# UI.net
KiCad netlist of a schematic drawn in EAGLE
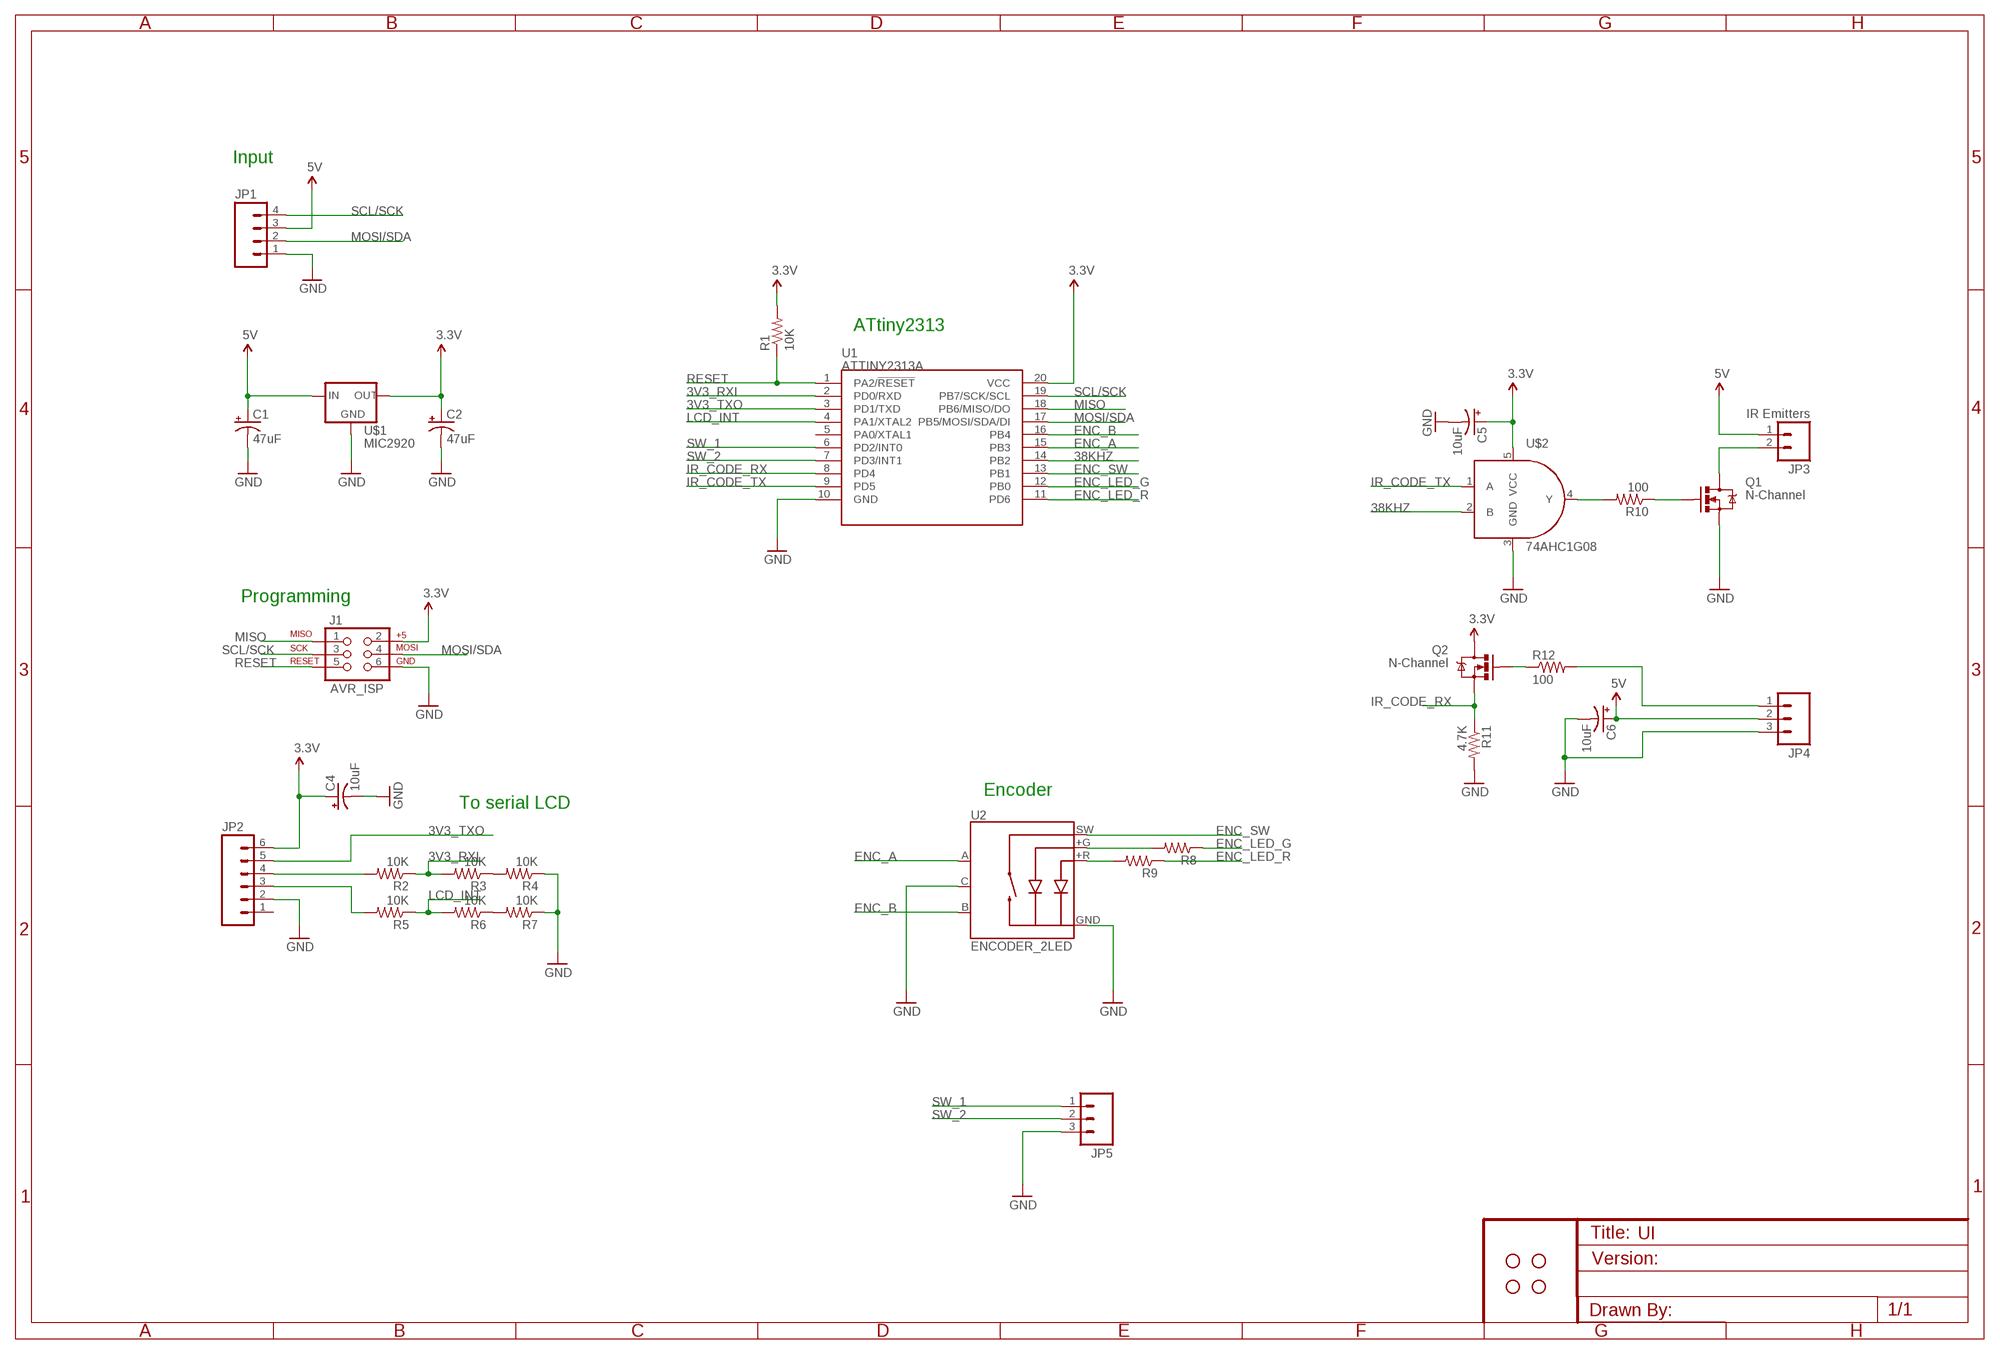
[diagram p0: schematic, sheet 1]

(export (version "E")
  (design (tool "Eeschema 10.0.6"))
  (components
    (comp (ref "C1")
      (value "47uF")
      (footprint "eagle-import:CPOL-RADIAL-10UF-25V")
      (libsource (lib "eagle-import") (part "CAP_POLPTH2"))
    )
    (comp (ref "C2")
      (value "47uF")
      (footprint "eagle-import:CPOL-RADIAL-10UF-25V")
      (libsource (lib "eagle-import") (part "CAP_POLPTH2"))
    )
    (comp (ref "C4")
      (value "10uF")
      (footprint "eagle-import:EIA3216")
      (libsource (lib "eagle-import") (part "CAP_POL1206"))
    )
    (comp (ref "C5")
      (value "10uF")
      (footprint "eagle-import:EIA3216")
      (libsource (lib "eagle-import") (part "CAP_POL1206"))
    )
    (comp (ref "C6")
      (value "10uF")
      (footprint "eagle-import:EIA3216")
      (libsource (lib "eagle-import") (part "CAP_POL1206"))
    )
    (comp (ref "J1")
      (value "AVR_ISP")
      (footprint "eagle-import:2X3")
      (libsource (lib "eagle-import") (part "AVR_SPI_PRG_6PTH"))
    )
    (comp (ref "JP1")
      (value "M04POLAR")
      (footprint "eagle-import:MOLEX-1X4")
      (libsource (lib "eagle-import") (part "M04POLAR"))
    )
    (comp (ref "JP2")
      (value "M06POLAR")
      (footprint "eagle-import:MOLEX-1X6")
      (libsource (lib "eagle-import") (part "M06POLAR"))
    )
    (comp (ref "JP3")
      (value "IR Emitters")
      (footprint "eagle-import:SCREWTERMINAL-3.5MM-2")
      (libsource (lib "eagle-import") (part "M023.5MM"))
    )
    (comp (ref "JP4")
      (value "M03PTH")
      (footprint "eagle-import:1X03")
      (libsource (lib "eagle-import") (part "M03PTH"))
    )
    (comp (ref "JP5")
      (value "M03PTH")
      (footprint "eagle-import:1X03")
      (libsource (lib "eagle-import") (part "M03PTH"))
    )
    (comp (ref "Q1")
      (value "N-Channel")
      (footprint "eagle-import:SOT23")
      (libsource (lib "eagle-import") (part "MOSFET-NCHANNELBSS138"))
    )
    (comp (ref "Q2")
      (value "N-Channel")
      (footprint "eagle-import:SOT23")
      (libsource (lib "eagle-import") (part "MOSFET-NCHANNELBSS138"))
    )
    (comp (ref "R1")
      (value "10K")
      (footprint "eagle-import:1206")
      (libsource (lib "eagle-import") (part "RESISTOR1206"))
    )
    (comp (ref "R2")
      (value "10K")
      (footprint "eagle-import:1206")
      (libsource (lib "eagle-import") (part "RESISTOR1206"))
    )
    (comp (ref "R3")
      (value "10K")
      (footprint "eagle-import:1206")
      (libsource (lib "eagle-import") (part "RESISTOR1206"))
    )
    (comp (ref "R4")
      (value "10K")
      (footprint "eagle-import:1206")
      (libsource (lib "eagle-import") (part "RESISTOR1206"))
    )
    (comp (ref "R5")
      (value "10K")
      (footprint "eagle-import:1206")
      (libsource (lib "eagle-import") (part "RESISTOR1206"))
    )
    (comp (ref "R6")
      (value "10K")
      (footprint "eagle-import:1206")
      (libsource (lib "eagle-import") (part "RESISTOR1206"))
    )
    (comp (ref "R7")
      (value "10K")
      (footprint "eagle-import:1206")
      (libsource (lib "eagle-import") (part "RESISTOR1206"))
    )
    (comp (ref "R8")
      (value "RESISTOR1206")
      (footprint "eagle-import:1206")
      (libsource (lib "eagle-import") (part "RESISTOR1206"))
    )
    (comp (ref "R9")
      (value "RESISTOR1206")
      (footprint "eagle-import:1206")
      (libsource (lib "eagle-import") (part "RESISTOR1206"))
    )
    (comp (ref "R10")
      (value "100")
      (footprint "eagle-import:1206")
      (libsource (lib "eagle-import") (part "RESISTOR1206"))
    )
    (comp (ref "R11")
      (value "4.7K")
      (footprint "eagle-import:1206")
      (libsource (lib "eagle-import") (part "RESISTOR1206"))
    )
    (comp (ref "R12")
      (value "100")
      (footprint "eagle-import:1206")
      (libsource (lib "eagle-import") (part "RESISTOR1206"))
    )
    (comp (ref "STANDOFF1")
      (value "STAND-OFF")
      (footprint "eagle-import:STAND-OFF")
      (libsource (lib "eagle-import") (part "STAND-OFF"))
    )
    (comp (ref "STANDOFF2")
      (value "STAND-OFF")
      (footprint "eagle-import:STAND-OFF")
      (libsource (lib "eagle-import") (part "STAND-OFF"))
    )
    (comp (ref "STANDOFF3")
      (value "STAND-OFF")
      (footprint "eagle-import:STAND-OFF")
      (libsource (lib "eagle-import") (part "STAND-OFF"))
    )
    (comp (ref "STANDOFF4")
      (value "STAND-OFF")
      (footprint "eagle-import:STAND-OFF")
      (libsource (lib "eagle-import") (part "STAND-OFF"))
    )
    (comp (ref "U$1")
      (value "MIC2920")
      (footprint "eagle-import:SOT223")
      (libsource (lib "eagle-import") (part "V_REG_MIC2920"))
    )
    (comp (ref "U$2")
      (value "74AHC1G08")
      (footprint "eagle-import:SOT23-5")
      (libsource (lib "eagle-import") (part "74AHC1G08"))
    )
    (comp (ref "U1")
      (value "ATTINY2313A")
      (footprint "eagle-import:SOP20W")
      (libsource (lib "eagle-import") (part "ATTINY2313A"))
    )
    (comp (ref "U2")
      (value "ENCODER_2LED")
      (footprint "eagle-import:ENCODER_LED_2")
      (libsource (lib "eagle-import") (part "ENCODER_2LED"))
    )
  )
  (nets
    (net (code "1") (name "/3V3_RXI") (class "Default")
      (node (ref "R2") (pin "1") (pinfunction "1_1") (pintype "passive"))
      (node (ref "R3") (pin "2") (pinfunction "2_2") (pintype "passive"))
      (node (ref "U1") (pin "2") (pinfunction "PD0/RXD_2") (pintype "bidirectional"))
    )
    (net (code "2") (name "/3V3_TXO") (class "Default")
      (node (ref "JP2") (pin "5") (pinfunction "5_5") (pintype "passive"))
      (node (ref "U1") (pin "3") (pinfunction "PD1/TXD_3") (pintype "bidirectional"))
    )
    (net (code "3") (name "/38KHZ") (class "Default")
      (node (ref "U$2") (pin "2") (pinfunction "B_2") (pintype "bidirectional"))
      (node (ref "U1") (pin "14") (pinfunction "PB2_14") (pintype "bidirectional"))
    )
    (net (code "4") (name "/ENC_A") (class "Default")
      (node (ref "U1") (pin "15") (pinfunction "PB3_15") (pintype "bidirectional"))
      (node (ref "U2") (pin "A") (pinfunction "A_A") (pintype "bidirectional"))
    )
    (net (code "5") (name "/ENC_B") (class "Default")
      (node (ref "U1") (pin "16") (pinfunction "PB4_16") (pintype "bidirectional"))
      (node (ref "U2") (pin "B") (pinfunction "B_B") (pintype "bidirectional"))
    )
    (net (code "6") (name "/ENC_LED_G") (class "Default")
      (node (ref "R8") (pin "1") (pinfunction "1_1") (pintype "passive"))
      (node (ref "U1") (pin "12") (pinfunction "PB0_12") (pintype "bidirectional"))
    )
    (net (code "7") (name "/ENC_LED_R") (class "Default")
      (node (ref "R9") (pin "1") (pinfunction "1_1") (pintype "passive"))
      (node (ref "U1") (pin "11") (pinfunction "PD6_11") (pintype "bidirectional"))
    )
    (net (code "8") (name "/ENC_SW") (class "Default")
      (node (ref "U1") (pin "13") (pinfunction "PB1_13") (pintype "bidirectional"))
      (node (ref "U2") (pin "SW") (pinfunction "SW_SW") (pintype "passive"))
    )
    (net (code "9") (name "/IR_CODE_RX") (class "Default")
      (node (ref "Q2") (pin "2") (pinfunction "S_2") (pintype "passive"))
      (node (ref "R11") (pin "1") (pinfunction "1_1") (pintype "passive"))
      (node (ref "U1") (pin "8") (pinfunction "PD4_8") (pintype "bidirectional"))
    )
    (net (code "10") (name "/IR_CODE_TX") (class "Default")
      (node (ref "U$2") (pin "1") (pinfunction "A_1") (pintype "bidirectional"))
      (node (ref "U1") (pin "9") (pinfunction "PD5_9") (pintype "bidirectional"))
    )
    (net (code "11") (name "/LCD_INT") (class "Default")
      (node (ref "R5") (pin "1") (pinfunction "1_1") (pintype "passive"))
      (node (ref "R6") (pin "2") (pinfunction "2_2") (pintype "passive"))
      (node (ref "U1") (pin "4") (pinfunction "PA1/XTAL2_4") (pintype "bidirectional"))
    )
    (net (code "12") (name "/MISO") (class "Default")
      (node (ref "J1") (pin "1") (pinfunction "1_1") (pintype "passive"))
      (node (ref "U1") (pin "18") (pinfunction "PB6/MISO/DO_18") (pintype "bidirectional"))
    )
    (net (code "13") (name "/MOSI{slash}SDA") (class "Default")
      (node (ref "J1") (pin "4") (pinfunction "4_4") (pintype "passive"))
      (node (ref "JP1") (pin "2") (pinfunction "2_2") (pintype "passive"))
      (node (ref "U1") (pin "17") (pinfunction "PB5/MOSI/SDA/DI_17") (pintype "bidirectional"))
    )
    (net (code "14") (name "/RESET") (class "Default")
      (node (ref "J1") (pin "5") (pinfunction "5_5") (pintype "passive"))
      (node (ref "R1") (pin "1") (pinfunction "1_1") (pintype "passive"))
      (node (ref "U1") (pin "1") (pinfunction "PA2/~{RESET}_1") (pintype "bidirectional"))
    )
    (net (code "15") (name "/SCL{slash}SCK") (class "Default")
      (node (ref "J1") (pin "3") (pinfunction "3_3") (pintype "passive"))
      (node (ref "JP1") (pin "4") (pinfunction "4_4") (pintype "passive"))
      (node (ref "U1") (pin "19") (pinfunction "PB7/SCK/SCL_19") (pintype "bidirectional"))
    )
    (net (code "16") (name "/SW_1") (class "Default")
      (node (ref "JP5") (pin "1") (pinfunction "1_1") (pintype "passive"))
      (node (ref "U1") (pin "6") (pinfunction "PD2/INT0_6") (pintype "bidirectional"))
    )
    (net (code "17") (name "/SW_2") (class "Default")
      (node (ref "JP5") (pin "2") (pinfunction "2_2") (pintype "passive"))
      (node (ref "U1") (pin "7") (pinfunction "PD3/INT1_7") (pintype "bidirectional"))
    )
    (net (code "18") (name "3.3V") (class "Default")
      (node (ref "C2") (pin "1") (pinfunction "+_1") (pintype "passive"))
      (node (ref "C4") (pin "A") (pinfunction "+_A") (pintype "passive"))
      (node (ref "C5") (pin "A") (pinfunction "+_A") (pintype "passive"))
      (node (ref "J1") (pin "2") (pinfunction "2_2") (pintype "passive"))
      (node (ref "JP2") (pin "6") (pinfunction "6_6") (pintype "passive"))
      (node (ref "Q2") (pin "3") (pinfunction "D_3") (pintype "passive"))
      (node (ref "R1") (pin "2") (pinfunction "2_2") (pintype "passive"))
      (node (ref "U$1") (pin "3") (pinfunction "OUT_3") (pintype "output"))
      (node (ref "U$2") (pin "5") (pinfunction "VCC_5") (pintype "bidirectional"))
      (node (ref "U1") (pin "20") (pinfunction "VCC_20") (pintype "bidirectional"))
    )
    (net (code "19") (name "5V") (class "Default")
      (node (ref "C1") (pin "1") (pinfunction "+_1") (pintype "passive"))
      (node (ref "C6") (pin "A") (pinfunction "+_A") (pintype "passive"))
      (node (ref "JP1") (pin "3") (pinfunction "3_3") (pintype "passive"))
      (node (ref "JP3") (pin "1") (pinfunction "1_1") (pintype "passive"))
      (node (ref "JP4") (pin "2") (pinfunction "2_2") (pintype "passive"))
      (node (ref "U$1") (pin "1") (pinfunction "IN_1") (pintype "input"))
    )
    (net (code "20") (name "GND") (class "Default")
      (node (ref "C1") (pin "2") (pinfunction "-_2") (pintype "passive"))
      (node (ref "C2") (pin "2") (pinfunction "-_2") (pintype "passive"))
      (node (ref "C4") (pin "C") (pinfunction "-_C") (pintype "passive"))
      (node (ref "C5") (pin "C") (pinfunction "-_C") (pintype "passive"))
      (node (ref "C6") (pin "C") (pinfunction "-_C") (pintype "passive"))
      (node (ref "J1") (pin "6") (pinfunction "6_6") (pintype "passive"))
      (node (ref "JP1") (pin "1") (pinfunction "1_1") (pintype "passive"))
      (node (ref "JP2") (pin "2") (pinfunction "2_2") (pintype "passive"))
      (node (ref "JP4") (pin "3") (pinfunction "3_3") (pintype "passive"))
      (node (ref "JP5") (pin "3") (pinfunction "3_3") (pintype "passive"))
      (node (ref "Q1") (pin "2") (pinfunction "S_2") (pintype "passive"))
      (node (ref "R11") (pin "2") (pinfunction "2_2") (pintype "passive"))
      (node (ref "R4") (pin "1") (pinfunction "1_1") (pintype "passive"))
      (node (ref "R7") (pin "1") (pinfunction "1_1") (pintype "passive"))
      (node (ref "U$1") (pin "2") (pinfunction "GND_2") (pintype "input"))
      (node (ref "U$2") (pin "3") (pinfunction "GND_3") (pintype "bidirectional"))
      (node (ref "U1") (pin "10") (pinfunction "GND_10") (pintype "bidirectional"))
      (node (ref "U2") (pin "C") (pinfunction "C_C") (pintype "bidirectional"))
      (node (ref "U2") (pin "GND") (pinfunction "-_GND") (pintype "passive"))
    )
    (net (code "21") (name "Net-(JP2-Pad3)") (class "Default")
      (node (ref "JP2") (pin "3") (pinfunction "3_3") (pintype "passive"))
      (node (ref "R5") (pin "2") (pinfunction "2_2") (pintype "passive"))
    )
    (net (code "22") (name "Net-(JP2-Pad4)") (class "Default")
      (node (ref "JP2") (pin "4") (pinfunction "4_4") (pintype "passive"))
      (node (ref "R2") (pin "2") (pinfunction "2_2") (pintype "passive"))
    )
    (net (code "23") (name "Net-(JP4-Pad1)") (class "Default")
      (node (ref "JP4") (pin "1") (pinfunction "1_1") (pintype "passive"))
      (node (ref "R12") (pin "2") (pinfunction "2_2") (pintype "passive"))
    )
    (net (code "24") (name "Net-(Q1-D)") (class "Default")
      (node (ref "JP3") (pin "2") (pinfunction "2_2") (pintype "passive"))
      (node (ref "Q1") (pin "3") (pinfunction "D_3") (pintype "passive"))
    )
    (net (code "25") (name "Net-(Q1-G)") (class "Default")
      (node (ref "Q1") (pin "1") (pinfunction "G_1") (pintype "passive"))
      (node (ref "R10") (pin "1") (pinfunction "1_1") (pintype "passive"))
    )
    (net (code "26") (name "Net-(Q2-G)") (class "Default")
      (node (ref "Q2") (pin "1") (pinfunction "G_1") (pintype "passive"))
      (node (ref "R12") (pin "1") (pinfunction "1_1") (pintype "passive"))
    )
    (net (code "27") (name "Net-(R3-Pad1)") (class "Default")
      (node (ref "R3") (pin "1") (pinfunction "1_1") (pintype "passive"))
      (node (ref "R4") (pin "2") (pinfunction "2_2") (pintype "passive"))
    )
    (net (code "28") (name "Net-(R6-Pad1)") (class "Default")
      (node (ref "R6") (pin "1") (pinfunction "1_1") (pintype "passive"))
      (node (ref "R7") (pin "2") (pinfunction "2_2") (pintype "passive"))
    )
    (net (code "29") (name "Net-(R8-Pad2)") (class "Default")
      (node (ref "R8") (pin "2") (pinfunction "2_2") (pintype "passive"))
      (node (ref "U2") (pin "+G") (pinfunction "+G_+G") (pintype "passive"))
    )
    (net (code "30") (name "Net-(R9-Pad2)") (class "Default")
      (node (ref "R9") (pin "2") (pinfunction "2_2") (pintype "passive"))
      (node (ref "U2") (pin "+R") (pinfunction "+R_+R") (pintype "passive"))
    )
    (net (code "31") (name "Net-(U$2-Y)") (class "Default")
      (node (ref "R10") (pin "2") (pinfunction "2_2") (pintype "passive"))
      (node (ref "U$2") (pin "4") (pinfunction "Y_4") (pintype "bidirectional"))
    )
    (net (code "32") (name "unconnected-(JP2-Pad1)") (class "Default")
      (node (ref "JP2") (pin "1") (pinfunction "1_1") (pintype "passive"))
    )
    (net (code "33") (name "unconnected-(U1-PA0{slash}XTAL1-Pad5)") (class "Default")
      (node (ref "U1") (pin "5") (pinfunction "PA0/XTAL1_5") (pintype "bidirectional"))
    )
  )
)
